# cpico_power.net
KiCad netlist of a schematic drawn in EAGLE
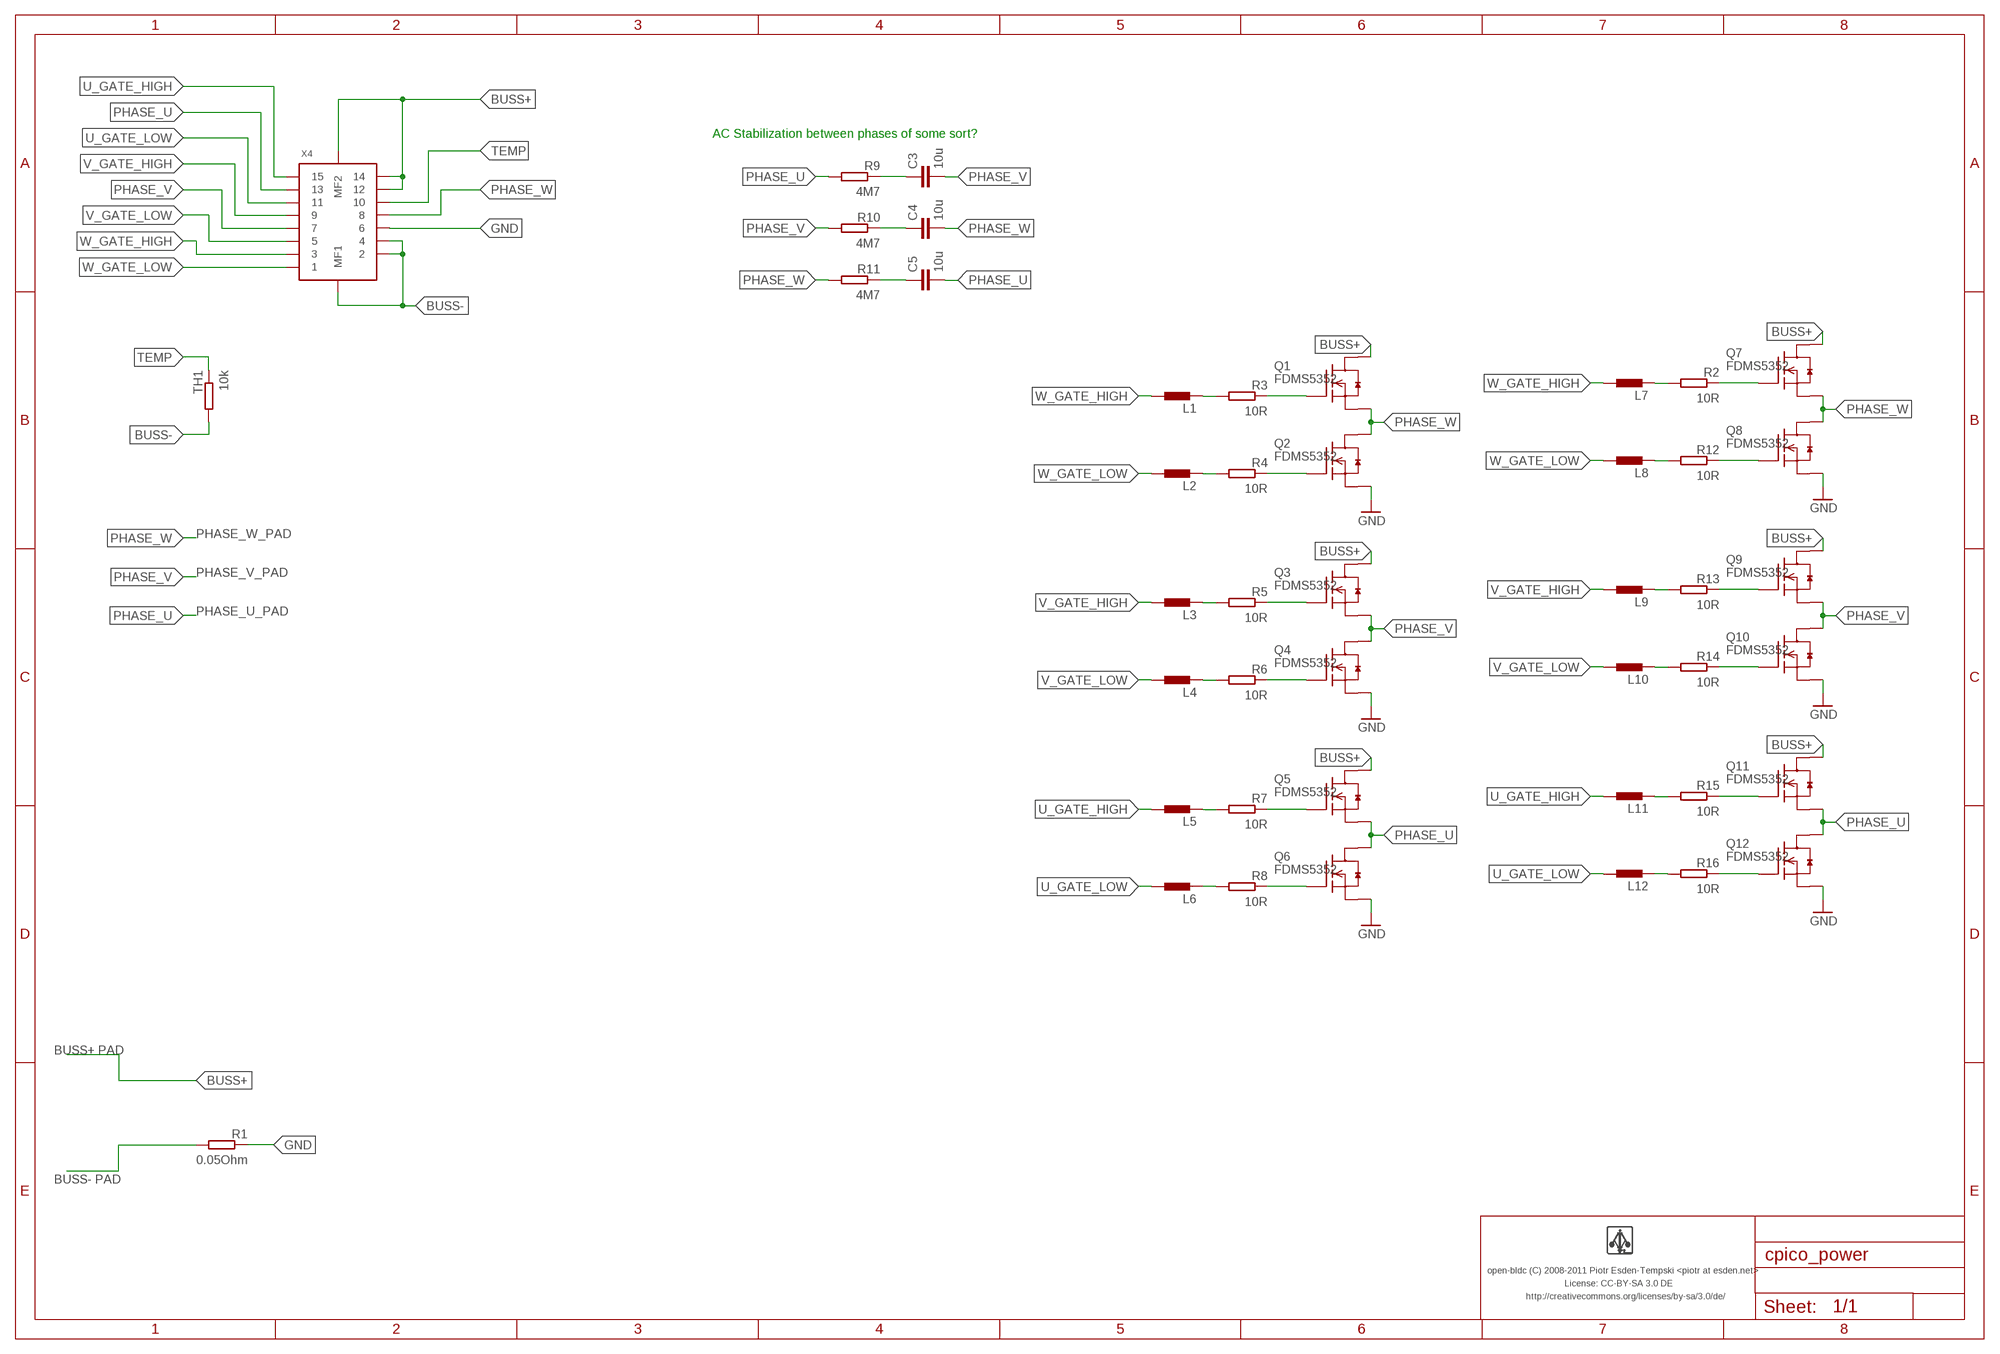
[diagram p0: schematic, sheet 1]

(export (version "E")
  (design (tool "Eeschema 10.0.6"))
  (components
    (comp (ref "C3")
      (value "10u")
      (footprint "eagle-import:0603-CAP")
      (libsource (lib "eagle-import") (part "CAPACITOR-0603"))
    )
    (comp (ref "C4")
      (value "10u")
      (footprint "eagle-import:0603-CAP")
      (libsource (lib "eagle-import") (part "CAPACITOR-0603"))
    )
    (comp (ref "C5")
      (value "10u")
      (footprint "eagle-import:0603-CAP")
      (libsource (lib "eagle-import") (part "CAPACITOR-0603"))
    )
    (comp (ref "L1")
      (value "INDUCTOR-0402")
      (footprint "eagle-import:0402-IND")
      (libsource (lib "eagle-import") (part "INDUCTOR-0402"))
    )
    (comp (ref "L2")
      (value "INDUCTOR-0402")
      (footprint "eagle-import:0402-IND")
      (libsource (lib "eagle-import") (part "INDUCTOR-0402"))
    )
    (comp (ref "L3")
      (value "INDUCTOR-0402")
      (footprint "eagle-import:0402-IND")
      (libsource (lib "eagle-import") (part "INDUCTOR-0402"))
    )
    (comp (ref "L4")
      (value "INDUCTOR-0402")
      (footprint "eagle-import:0402-IND")
      (libsource (lib "eagle-import") (part "INDUCTOR-0402"))
    )
    (comp (ref "L5")
      (value "INDUCTOR-0402")
      (footprint "eagle-import:0402-IND")
      (libsource (lib "eagle-import") (part "INDUCTOR-0402"))
    )
    (comp (ref "L6")
      (value "INDUCTOR-0402")
      (footprint "eagle-import:0402-IND")
      (libsource (lib "eagle-import") (part "INDUCTOR-0402"))
    )
    (comp (ref "L7")
      (value "INDUCTOR-0402")
      (footprint "eagle-import:0402-IND")
      (libsource (lib "eagle-import") (part "INDUCTOR-0402"))
    )
    (comp (ref "L8")
      (value "INDUCTOR-0402")
      (footprint "eagle-import:0402-IND")
      (libsource (lib "eagle-import") (part "INDUCTOR-0402"))
    )
    (comp (ref "L9")
      (value "INDUCTOR-0402")
      (footprint "eagle-import:0402-IND")
      (libsource (lib "eagle-import") (part "INDUCTOR-0402"))
    )
    (comp (ref "L10")
      (value "INDUCTOR-0402")
      (footprint "eagle-import:0402-IND")
      (libsource (lib "eagle-import") (part "INDUCTOR-0402"))
    )
    (comp (ref "L11")
      (value "INDUCTOR-0402")
      (footprint "eagle-import:0402-IND")
      (libsource (lib "eagle-import") (part "INDUCTOR-0402"))
    )
    (comp (ref "L12")
      (value "INDUCTOR-0402")
      (footprint "eagle-import:0402-IND")
      (libsource (lib "eagle-import") (part "INDUCTOR-0402"))
    )
    (comp (ref "Q1")
      (value "FDMS5352")
      (footprint "eagle-import:MSL1")
      (libsource (lib "eagle-import") (part "FDMS5352"))
    )
    (comp (ref "Q2")
      (value "FDMS5352")
      (footprint "eagle-import:MSL1")
      (libsource (lib "eagle-import") (part "FDMS5352"))
    )
    (comp (ref "Q3")
      (value "FDMS5352")
      (footprint "eagle-import:MSL1")
      (libsource (lib "eagle-import") (part "FDMS5352"))
    )
    (comp (ref "Q4")
      (value "FDMS5352")
      (footprint "eagle-import:MSL1")
      (libsource (lib "eagle-import") (part "FDMS5352"))
    )
    (comp (ref "Q5")
      (value "FDMS5352")
      (footprint "eagle-import:MSL1")
      (libsource (lib "eagle-import") (part "FDMS5352"))
    )
    (comp (ref "Q6")
      (value "FDMS5352")
      (footprint "eagle-import:MSL1")
      (libsource (lib "eagle-import") (part "FDMS5352"))
    )
    (comp (ref "Q7")
      (value "FDMS5352")
      (footprint "eagle-import:MSL1")
      (libsource (lib "eagle-import") (part "FDMS5352"))
    )
    (comp (ref "Q8")
      (value "FDMS5352")
      (footprint "eagle-import:MSL1")
      (libsource (lib "eagle-import") (part "FDMS5352"))
    )
    (comp (ref "Q9")
      (value "FDMS5352")
      (footprint "eagle-import:MSL1")
      (libsource (lib "eagle-import") (part "FDMS5352"))
    )
    (comp (ref "Q10")
      (value "FDMS5352")
      (footprint "eagle-import:MSL1")
      (libsource (lib "eagle-import") (part "FDMS5352"))
    )
    (comp (ref "Q11")
      (value "FDMS5352")
      (footprint "eagle-import:MSL1")
      (libsource (lib "eagle-import") (part "FDMS5352"))
    )
    (comp (ref "Q12")
      (value "FDMS5352")
      (footprint "eagle-import:MSL1")
      (libsource (lib "eagle-import") (part "FDMS5352"))
    )
    (comp (ref "R1")
      (value "0.05Ohm")
      (footprint "eagle-import:1206-RES")
      (libsource (lib "eagle-import") (part "RESISTOR-1206"))
    )
    (comp (ref "R2")
      (value "10R")
      (footprint "eagle-import:0402-RES")
      (libsource (lib "eagle-import") (part "RESISTOR-0402"))
    )
    (comp (ref "R3")
      (value "10R")
      (footprint "eagle-import:0402-RES")
      (libsource (lib "eagle-import") (part "RESISTOR-0402"))
    )
    (comp (ref "R4")
      (value "10R")
      (footprint "eagle-import:0402-RES")
      (libsource (lib "eagle-import") (part "RESISTOR-0402"))
    )
    (comp (ref "R5")
      (value "10R")
      (footprint "eagle-import:0402-RES")
      (libsource (lib "eagle-import") (part "RESISTOR-0402"))
    )
    (comp (ref "R6")
      (value "10R")
      (footprint "eagle-import:0402-RES")
      (libsource (lib "eagle-import") (part "RESISTOR-0402"))
    )
    (comp (ref "R7")
      (value "10R")
      (footprint "eagle-import:0402-RES")
      (libsource (lib "eagle-import") (part "RESISTOR-0402"))
    )
    (comp (ref "R8")
      (value "10R")
      (footprint "eagle-import:0402-RES")
      (libsource (lib "eagle-import") (part "RESISTOR-0402"))
    )
    (comp (ref "R9")
      (value "4M7")
      (footprint "eagle-import:0603-RES")
      (libsource (lib "eagle-import") (part "RESISTOR-0603"))
    )
    (comp (ref "R10")
      (value "4M7")
      (footprint "eagle-import:0603-RES")
      (libsource (lib "eagle-import") (part "RESISTOR-0603"))
    )
    (comp (ref "R11")
      (value "4M7")
      (footprint "eagle-import:0603-RES")
      (libsource (lib "eagle-import") (part "RESISTOR-0603"))
    )
    (comp (ref "R12")
      (value "10R")
      (footprint "eagle-import:0402-RES")
      (libsource (lib "eagle-import") (part "RESISTOR-0402"))
    )
    (comp (ref "R13")
      (value "10R")
      (footprint "eagle-import:0402-RES")
      (libsource (lib "eagle-import") (part "RESISTOR-0402"))
    )
    (comp (ref "R14")
      (value "10R")
      (footprint "eagle-import:0402-RES")
      (libsource (lib "eagle-import") (part "RESISTOR-0402"))
    )
    (comp (ref "R15")
      (value "10R")
      (footprint "eagle-import:0402-RES")
      (libsource (lib "eagle-import") (part "RESISTOR-0402"))
    )
    (comp (ref "R16")
      (value "10R")
      (footprint "eagle-import:0402-RES")
      (libsource (lib "eagle-import") (part "RESISTOR-0402"))
    )
    (comp (ref "TH1")
      (value "10k")
      (footprint "eagle-import:0603-RES")
      (libsource (lib "eagle-import") (part "RESISTOR-0603"))
    )
    (comp (ref "U$2")
      (value "LOGO-NORM")
      (footprint "eagle-import:LOGO")
      (libsource (lib "eagle-import") (part "LOGO-NORM"))
    )
    (comp (ref "X4")
      (value "CONN_15-2-2MT-DF9")
      (footprint "eagle-import:DF9-15")
      (libsource (lib "eagle-import") (part "CONN_15-2-2MT-DF9"))
    )
  )
  (nets
    (net (code "1") (name "BUSS+") (class "Default")
      (node (ref "Q1") (pin "3") (pinfunction "D_3") (pintype "passive"))
      (node (ref "Q11") (pin "3") (pinfunction "D_3") (pintype "passive"))
      (node (ref "Q3") (pin "3") (pinfunction "D_3") (pintype "passive"))
      (node (ref "Q5") (pin "3") (pinfunction "D_3") (pintype "passive"))
      (node (ref "Q7") (pin "3") (pinfunction "D_3") (pintype "passive"))
      (node (ref "Q9") (pin "3") (pinfunction "D_3") (pintype "passive"))
      (node (ref "X4") (pin "12") (pinfunction "12_12") (pintype "bidirectional"))
      (node (ref "X4") (pin "14") (pinfunction "14_14") (pintype "bidirectional"))
      (node (ref "X4") (pin "MF2") (pinfunction "MF2_MF2") (pintype "bidirectional"))
    )
    (net (code "2") (name "BUSS-") (class "Default")
      (node (ref "R1") (pin "P$2") (pinfunction "2_P$2") (pintype "passive"))
      (node (ref "TH1") (pin "P$2") (pinfunction "2_P$2") (pintype "passive"))
      (node (ref "X4") (pin "2") (pinfunction "2_2") (pintype "bidirectional"))
      (node (ref "X4") (pin "4") (pinfunction "4_4") (pintype "bidirectional"))
      (node (ref "X4") (pin "MF1") (pinfunction "MF1_MF1") (pintype "bidirectional"))
    )
    (net (code "3") (name "GND") (class "Default")
      (node (ref "Q10") (pin "1") (pinfunction "S_1") (pintype "passive"))
      (node (ref "Q12") (pin "1") (pinfunction "S_1") (pintype "passive"))
      (node (ref "Q2") (pin "1") (pinfunction "S_1") (pintype "passive"))
      (node (ref "Q4") (pin "1") (pinfunction "S_1") (pintype "passive"))
      (node (ref "Q6") (pin "1") (pinfunction "S_1") (pintype "passive"))
      (node (ref "Q8") (pin "1") (pinfunction "S_1") (pintype "passive"))
      (node (ref "R1") (pin "P$1") (pinfunction "1_P$1") (pintype "passive"))
      (node (ref "X4") (pin "6") (pinfunction "6_6") (pintype "bidirectional"))
    )
    (net (code "4") (name "Net-(C3-1)") (class "Default")
      (node (ref "C3") (pin "P$1") (pinfunction "1_P$1") (pintype "passive"))
      (node (ref "R9") (pin "P$1") (pinfunction "1_P$1") (pintype "passive"))
    )
    (net (code "5") (name "Net-(C4-1)") (class "Default")
      (node (ref "C4") (pin "P$1") (pinfunction "1_P$1") (pintype "passive"))
      (node (ref "R10") (pin "P$1") (pinfunction "1_P$1") (pintype "passive"))
    )
    (net (code "6") (name "Net-(C5-1)") (class "Default")
      (node (ref "C5") (pin "P$1") (pinfunction "1_P$1") (pintype "passive"))
      (node (ref "R11") (pin "P$1") (pinfunction "1_P$1") (pintype "passive"))
    )
    (net (code "7") (name "Net-(L1-2)") (class "Default")
      (node (ref "L1") (pin "P$2") (pinfunction "2_P$2") (pintype "passive"))
      (node (ref "R3") (pin "P$2") (pinfunction "2_P$2") (pintype "passive"))
    )
    (net (code "8") (name "Net-(L2-2)") (class "Default")
      (node (ref "L2") (pin "P$2") (pinfunction "2_P$2") (pintype "passive"))
      (node (ref "R4") (pin "P$2") (pinfunction "2_P$2") (pintype "passive"))
    )
    (net (code "9") (name "Net-(L3-2)") (class "Default")
      (node (ref "L3") (pin "P$2") (pinfunction "2_P$2") (pintype "passive"))
      (node (ref "R5") (pin "P$2") (pinfunction "2_P$2") (pintype "passive"))
    )
    (net (code "10") (name "Net-(L4-2)") (class "Default")
      (node (ref "L4") (pin "P$2") (pinfunction "2_P$2") (pintype "passive"))
      (node (ref "R6") (pin "P$2") (pinfunction "2_P$2") (pintype "passive"))
    )
    (net (code "11") (name "Net-(L5-2)") (class "Default")
      (node (ref "L5") (pin "P$2") (pinfunction "2_P$2") (pintype "passive"))
      (node (ref "R7") (pin "P$2") (pinfunction "2_P$2") (pintype "passive"))
    )
    (net (code "12") (name "Net-(L6-2)") (class "Default")
      (node (ref "L6") (pin "P$2") (pinfunction "2_P$2") (pintype "passive"))
      (node (ref "R8") (pin "P$2") (pinfunction "2_P$2") (pintype "passive"))
    )
    (net (code "13") (name "Net-(L7-2)") (class "Default")
      (node (ref "L7") (pin "P$2") (pinfunction "2_P$2") (pintype "passive"))
      (node (ref "R2") (pin "P$2") (pinfunction "2_P$2") (pintype "passive"))
    )
    (net (code "14") (name "Net-(L8-2)") (class "Default")
      (node (ref "L8") (pin "P$2") (pinfunction "2_P$2") (pintype "passive"))
      (node (ref "R12") (pin "P$2") (pinfunction "2_P$2") (pintype "passive"))
    )
    (net (code "15") (name "Net-(L9-2)") (class "Default")
      (node (ref "L9") (pin "P$2") (pinfunction "2_P$2") (pintype "passive"))
      (node (ref "R13") (pin "P$2") (pinfunction "2_P$2") (pintype "passive"))
    )
    (net (code "16") (name "Net-(L10-2)") (class "Default")
      (node (ref "L10") (pin "P$2") (pinfunction "2_P$2") (pintype "passive"))
      (node (ref "R14") (pin "P$2") (pinfunction "2_P$2") (pintype "passive"))
    )
    (net (code "17") (name "Net-(L11-2)") (class "Default")
      (node (ref "L11") (pin "P$2") (pinfunction "2_P$2") (pintype "passive"))
      (node (ref "R15") (pin "P$2") (pinfunction "2_P$2") (pintype "passive"))
    )
    (net (code "18") (name "Net-(L12-2)") (class "Default")
      (node (ref "L12") (pin "P$2") (pinfunction "2_P$2") (pintype "passive"))
      (node (ref "R16") (pin "P$2") (pinfunction "2_P$2") (pintype "passive"))
    )
    (net (code "19") (name "Net-(Q1-G)") (class "Default")
      (node (ref "Q1") (pin "2") (pinfunction "G_2") (pintype "passive"))
      (node (ref "R3") (pin "P$1") (pinfunction "1_P$1") (pintype "passive"))
    )
    (net (code "20") (name "Net-(Q2-G)") (class "Default")
      (node (ref "Q2") (pin "2") (pinfunction "G_2") (pintype "passive"))
      (node (ref "R4") (pin "P$1") (pinfunction "1_P$1") (pintype "passive"))
    )
    (net (code "21") (name "Net-(Q3-G)") (class "Default")
      (node (ref "Q3") (pin "2") (pinfunction "G_2") (pintype "passive"))
      (node (ref "R5") (pin "P$1") (pinfunction "1_P$1") (pintype "passive"))
    )
    (net (code "22") (name "Net-(Q4-G)") (class "Default")
      (node (ref "Q4") (pin "2") (pinfunction "G_2") (pintype "passive"))
      (node (ref "R6") (pin "P$1") (pinfunction "1_P$1") (pintype "passive"))
    )
    (net (code "23") (name "Net-(Q5-G)") (class "Default")
      (node (ref "Q5") (pin "2") (pinfunction "G_2") (pintype "passive"))
      (node (ref "R7") (pin "P$1") (pinfunction "1_P$1") (pintype "passive"))
    )
    (net (code "24") (name "Net-(Q6-G)") (class "Default")
      (node (ref "Q6") (pin "2") (pinfunction "G_2") (pintype "passive"))
      (node (ref "R8") (pin "P$1") (pinfunction "1_P$1") (pintype "passive"))
    )
    (net (code "25") (name "Net-(Q7-G)") (class "Default")
      (node (ref "Q7") (pin "2") (pinfunction "G_2") (pintype "passive"))
      (node (ref "R2") (pin "P$1") (pinfunction "1_P$1") (pintype "passive"))
    )
    (net (code "26") (name "Net-(Q8-G)") (class "Default")
      (node (ref "Q8") (pin "2") (pinfunction "G_2") (pintype "passive"))
      (node (ref "R12") (pin "P$1") (pinfunction "1_P$1") (pintype "passive"))
    )
    (net (code "27") (name "Net-(Q9-G)") (class "Default")
      (node (ref "Q9") (pin "2") (pinfunction "G_2") (pintype "passive"))
      (node (ref "R13") (pin "P$1") (pinfunction "1_P$1") (pintype "passive"))
    )
    (net (code "28") (name "Net-(Q10-G)") (class "Default")
      (node (ref "Q10") (pin "2") (pinfunction "G_2") (pintype "passive"))
      (node (ref "R14") (pin "P$1") (pinfunction "1_P$1") (pintype "passive"))
    )
    (net (code "29") (name "Net-(Q11-G)") (class "Default")
      (node (ref "Q11") (pin "2") (pinfunction "G_2") (pintype "passive"))
      (node (ref "R15") (pin "P$1") (pinfunction "1_P$1") (pintype "passive"))
    )
    (net (code "30") (name "Net-(Q12-G)") (class "Default")
      (node (ref "Q12") (pin "2") (pinfunction "G_2") (pintype "passive"))
      (node (ref "R16") (pin "P$1") (pinfunction "1_P$1") (pintype "passive"))
    )
    (net (code "31") (name "PHASE_U") (class "Default")
      (node (ref "C5") (pin "P$2") (pinfunction "2_P$2") (pintype "passive"))
      (node (ref "Q11") (pin "1") (pinfunction "S_1") (pintype "passive"))
      (node (ref "Q12") (pin "3") (pinfunction "D_3") (pintype "passive"))
      (node (ref "Q5") (pin "1") (pinfunction "S_1") (pintype "passive"))
      (node (ref "Q6") (pin "3") (pinfunction "D_3") (pintype "passive"))
      (node (ref "R9") (pin "P$2") (pinfunction "2_P$2") (pintype "passive"))
      (node (ref "X4") (pin "13") (pinfunction "13_13") (pintype "bidirectional"))
    )
    (net (code "32") (name "PHASE_V") (class "Default")
      (node (ref "C3") (pin "P$2") (pinfunction "2_P$2") (pintype "passive"))
      (node (ref "Q10") (pin "3") (pinfunction "D_3") (pintype "passive"))
      (node (ref "Q3") (pin "1") (pinfunction "S_1") (pintype "passive"))
      (node (ref "Q4") (pin "3") (pinfunction "D_3") (pintype "passive"))
      (node (ref "Q9") (pin "1") (pinfunction "S_1") (pintype "passive"))
      (node (ref "R10") (pin "P$2") (pinfunction "2_P$2") (pintype "passive"))
      (node (ref "X4") (pin "7") (pinfunction "7_7") (pintype "bidirectional"))
    )
    (net (code "33") (name "PHASE_W") (class "Default")
      (node (ref "C4") (pin "P$2") (pinfunction "2_P$2") (pintype "passive"))
      (node (ref "Q1") (pin "1") (pinfunction "S_1") (pintype "passive"))
      (node (ref "Q2") (pin "3") (pinfunction "D_3") (pintype "passive"))
      (node (ref "Q7") (pin "1") (pinfunction "S_1") (pintype "passive"))
      (node (ref "Q8") (pin "3") (pinfunction "D_3") (pintype "passive"))
      (node (ref "R11") (pin "P$2") (pinfunction "2_P$2") (pintype "passive"))
      (node (ref "X4") (pin "8") (pinfunction "8_8") (pintype "bidirectional"))
    )
    (net (code "34") (name "TEMP") (class "Default")
      (node (ref "TH1") (pin "P$1") (pinfunction "1_P$1") (pintype "passive"))
      (node (ref "X4") (pin "10") (pinfunction "10_10") (pintype "bidirectional"))
    )
    (net (code "35") (name "U_GATE_HIGH") (class "Default")
      (node (ref "L11") (pin "P$1") (pinfunction "1_P$1") (pintype "passive"))
      (node (ref "L5") (pin "P$1") (pinfunction "1_P$1") (pintype "passive"))
      (node (ref "X4") (pin "15") (pinfunction "15_15") (pintype "bidirectional"))
    )
    (net (code "36") (name "U_GATE_LOW") (class "Default")
      (node (ref "L12") (pin "P$1") (pinfunction "1_P$1") (pintype "passive"))
      (node (ref "L6") (pin "P$1") (pinfunction "1_P$1") (pintype "passive"))
      (node (ref "X4") (pin "11") (pinfunction "11_11") (pintype "bidirectional"))
    )
    (net (code "37") (name "V_GATE_HIGH") (class "Default")
      (node (ref "L3") (pin "P$1") (pinfunction "1_P$1") (pintype "passive"))
      (node (ref "L9") (pin "P$1") (pinfunction "1_P$1") (pintype "passive"))
      (node (ref "X4") (pin "9") (pinfunction "9_9") (pintype "bidirectional"))
    )
    (net (code "38") (name "V_GATE_LOW") (class "Default")
      (node (ref "L10") (pin "P$1") (pinfunction "1_P$1") (pintype "passive"))
      (node (ref "L4") (pin "P$1") (pinfunction "1_P$1") (pintype "passive"))
      (node (ref "X4") (pin "5") (pinfunction "5_5") (pintype "bidirectional"))
    )
    (net (code "39") (name "W_GATE_HIGH") (class "Default")
      (node (ref "L1") (pin "P$1") (pinfunction "1_P$1") (pintype "passive"))
      (node (ref "L7") (pin "P$1") (pinfunction "1_P$1") (pintype "passive"))
      (node (ref "X4") (pin "3") (pinfunction "3_3") (pintype "bidirectional"))
    )
    (net (code "40") (name "W_GATE_LOW") (class "Default")
      (node (ref "L2") (pin "P$1") (pinfunction "1_P$1") (pintype "passive"))
      (node (ref "L8") (pin "P$1") (pinfunction "1_P$1") (pintype "passive"))
      (node (ref "X4") (pin "1") (pinfunction "1_1") (pintype "bidirectional"))
    )
  )
)
